# auto_dtm.net
KiCad netlist of a schematic drawn in EAGLE
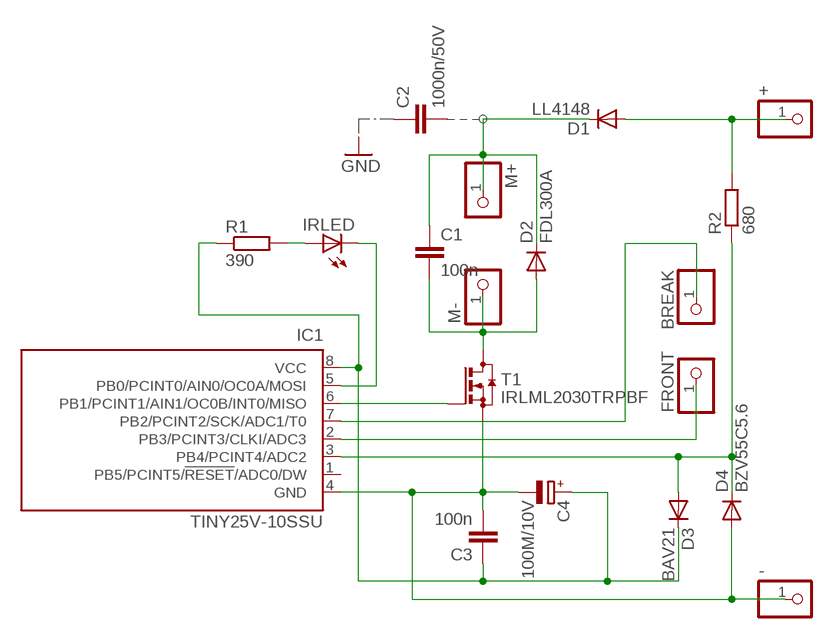
[diagram p0: schematic, sheet 1]

(export (version "E")
  (design (tool "Eeschema 10.0.6"))
  (components
    (comp (ref "+")
      (value "PINHD-1X1")
      (footprint "eagle-import:1X01")
      (libsource (lib "eagle-import") (part "PINHD-1X1"))
    )
    (comp (ref "-")
      (value "PINHD-1X1")
      (footprint "eagle-import:1X01")
      (libsource (lib "eagle-import") (part "PINHD-1X1"))
    )
    (comp (ref "BREAK")
      (value "PINHD-1X1")
      (footprint "eagle-import:1X01")
      (libsource (lib "eagle-import") (part "PINHD-1X1"))
    )
    (comp (ref "C1")
      (value "100n")
      (footprint "eagle-import:C1206")
      (libsource (lib "eagle-import") (part "C-EUC1206"))
    )
    (comp (ref "C2")
      (value "1000n/50V")
      (footprint "eagle-import:C025-024X044")
      (libsource (lib "eagle-import") (part "C-EU025-024X044"))
    )
    (comp (ref "C3")
      (value "100n")
      (footprint "eagle-import:C1206")
      (libsource (lib "eagle-import") (part "C-EUC1206"))
    )
    (comp (ref "C4")
      (value "100M/10V")
      (footprint "eagle-import:SMC_C")
      (libsource (lib "eagle-import") (part "CPOL-EUSMCC"))
    )
    (comp (ref "D1")
      (value "LL4148")
      (footprint "eagle-import:MINIMELF")
      (libsource (lib "eagle-import") (part "DIODE-MINIMELF"))
    )
    (comp (ref "D2")
      (value "FDL300A")
      (footprint "eagle-import:MINIMELF")
      (libsource (lib "eagle-import") (part "DIODE-MINIMELF"))
    )
    (comp (ref "D3")
      (value "BAV21")
      (footprint "eagle-import:MINIMELF")
      (libsource (lib "eagle-import") (part "DIODE-MINIMELF"))
    )
    (comp (ref "D4")
      (value "BZV55C5.6")
      (footprint "eagle-import:MINIMELF")
      (libsource (lib "eagle-import") (part "DIODE-MINIMELF"))
    )
    (comp (ref "FRONT")
      (value "PINHD-1X1")
      (footprint "eagle-import:1X01")
      (libsource (lib "eagle-import") (part "PINHD-1X1"))
    )
    (comp (ref "IC1")
      (value "TINY25V-10SSU")
      (footprint "eagle-import:8S1")
      (fields (field (name "MPN") "ATTINY13-20SSU"))
      (libsource (lib "eagle-import") (part "TINY13SSU-20"))
    )
    (comp (ref "IRLED")
      (value "LED3MM")
      (footprint "eagle-import:LED3MM")
      (libsource (lib "eagle-import") (part "LED3MM"))
    )
    (comp (ref "M+")
      (value "PINHD-1X1")
      (footprint "eagle-import:1X01")
      (libsource (lib "eagle-import") (part "PINHD-1X1"))
    )
    (comp (ref "M-")
      (value "PINHD-1X1")
      (footprint "eagle-import:1X01")
      (libsource (lib "eagle-import") (part "PINHD-1X1"))
    )
    (comp (ref "R1")
      (value "390")
      (footprint "eagle-import:R1206")
      (libsource (lib "eagle-import") (part "R-EU_R1206"))
    )
    (comp (ref "R2")
      (value "680")
      (footprint "eagle-import:R1206")
      (libsource (lib "eagle-import") (part "R-EU_R1206"))
    )
    (comp (ref "T1")
      (value "IRLML2030TRPBF")
      (footprint "eagle-import:SOT23")
      (libsource (lib "eagle-import") (part "BSS123"))
    )
  )
  (nets
    (net (code "2") (name "Net-(+-Pad1)") (class "Default")
      (node (ref "+") (pin "1") (pinfunction "1_1") (pintype "passive"))
      (node (ref "D1") (pin "A") (pinfunction "A_A") (pintype "passive"))
      (node (ref "R2") (pin "2") (pinfunction "2_2") (pintype "passive"))
    )
    (net (code "3") (name "Net-(C1-Pad1)") (class "Default")
      (node (ref "C1") (pin "1") (pinfunction "1_1") (pintype "passive"))
      (node (ref "D1") (pin "C") (pinfunction "C_C") (pintype "passive"))
      (node (ref "D2") (pin "C") (pinfunction "C_C") (pintype "passive"))
      (node (ref "M+") (pin "1") (pinfunction "1_1") (pintype "passive"))
    )
    (net (code "4") (name "Net-(IC1-GND)") (class "Default")
      (node (ref "-") (pin "1") (pinfunction "1_1") (pintype "passive"))
      (node (ref "C3") (pin "2") (pinfunction "2_2") (pintype "passive"))
      (node (ref "C4") (pin "-") (pinfunction "-_-") (pintype "passive"))
      (node (ref "D4") (pin "A") (pinfunction "A_A") (pintype "passive"))
      (node (ref "IC1") (pin "4") (pinfunction "GND_4") (pintype "power_in"))
      (node (ref "T1") (pin "2") (pinfunction "S_2") (pintype "passive"))
    )
    (net (code "5") (name "Net-(IC1-PB0{slash}PCINT0{slash}AIN0{slash}OC0A{slash}MOSI)") (class "Default")
      (node (ref "IC1") (pin "5") (pinfunction "PB0/PCINT0/AIN0/OC0A/MOSI_5") (pintype "bidirectional"))
      (node (ref "IRLED") (pin "K") (pinfunction "C_K") (pintype "passive"))
    )
    (net (code "6") (name "Net-(IC1-PB1{slash}PCINT1{slash}AIN1{slash}OC0B{slash}INT0{slash}MISO)") (class "Default")
      (node (ref "IC1") (pin "6") (pinfunction "PB1/PCINT1/AIN1/OC0B/INT0/MISO_6") (pintype "bidirectional"))
      (node (ref "T1") (pin "1") (pinfunction "G_1") (pintype "passive"))
    )
    (net (code "7") (name "Net-(IC1-PB2{slash}PCINT2{slash}SCK{slash}ADC1{slash}T0)") (class "Default")
      (node (ref "BREAK") (pin "1") (pinfunction "1_1") (pintype "passive"))
      (node (ref "IC1") (pin "7") (pinfunction "PB2/PCINT2/SCK/ADC1/T0_7") (pintype "bidirectional"))
    )
    (net (code "8") (name "Net-(IC1-PB3{slash}PCINT3{slash}CLKI{slash}ADC3)") (class "Default")
      (node (ref "FRONT") (pin "1") (pinfunction "1_1") (pintype "passive"))
      (node (ref "IC1") (pin "2") (pinfunction "PB3/PCINT3/CLKI/ADC3_2") (pintype "bidirectional"))
    )
    (net (code "9") (name "Net-(IC1-PB4{slash}PCINT4{slash}ADC2)") (class "Default")
      (node (ref "D3") (pin "A") (pinfunction "A_A") (pintype "passive"))
      (node (ref "D4") (pin "C") (pinfunction "C_C") (pintype "passive"))
      (node (ref "IC1") (pin "3") (pinfunction "PB4/PCINT4/ADC2_3") (pintype "bidirectional"))
      (node (ref "R2") (pin "1") (pinfunction "1_1") (pintype "passive"))
    )
    (net (code "10") (name "Net-(IC1-VCC)") (class "Default")
      (node (ref "C3") (pin "1") (pinfunction "1_1") (pintype "passive"))
      (node (ref "C4") (pin "+") (pinfunction "+_+") (pintype "passive"))
      (node (ref "D3") (pin "C") (pinfunction "C_C") (pintype "passive"))
      (node (ref "IC1") (pin "8") (pinfunction "VCC_8") (pintype "power_in"))
      (node (ref "R1") (pin "1") (pinfunction "1_1") (pintype "passive"))
    )
    (net (code "11") (name "Net-(IRLED-PadA)") (class "Default")
      (node (ref "IRLED") (pin "A") (pinfunction "A_A") (pintype "passive"))
      (node (ref "R1") (pin "2") (pinfunction "2_2") (pintype "passive"))
    )
    (net (code "12") (name "Net-(T1-D)") (class "Default")
      (node (ref "C1") (pin "2") (pinfunction "2_2") (pintype "passive"))
      (node (ref "D2") (pin "A") (pinfunction "A_A") (pintype "passive"))
      (node (ref "M-") (pin "1") (pinfunction "1_1") (pintype "passive"))
      (node (ref "T1") (pin "3") (pinfunction "D_3") (pintype "passive"))
    )
    (net (code "13") (name "unconnected-(C2-Pad1)") (class "Default")
      (node (ref "C2") (pin "1") (pinfunction "1_1") (pintype "passive"))
    )
    (net (code "14") (name "unconnected-(C2-Pad2)") (class "Default")
      (node (ref "C2") (pin "2") (pinfunction "2_2") (pintype "passive"))
    )
    (net (code "15") (name "unconnected-(IC1-PB5{slash}PCINT5{slash}~{RESET}{slash}ADC0{slash}DW-Pad1)") (class "Default")
      (node (ref "IC1") (pin "1") (pinfunction "PB5/PCINT5/~{RESET}/ADC0/DW_1") (pintype "bidirectional"))
    )
  )
)
